# Sheet1.net
KiCad netlist of a schematic drawn in Altium Designer
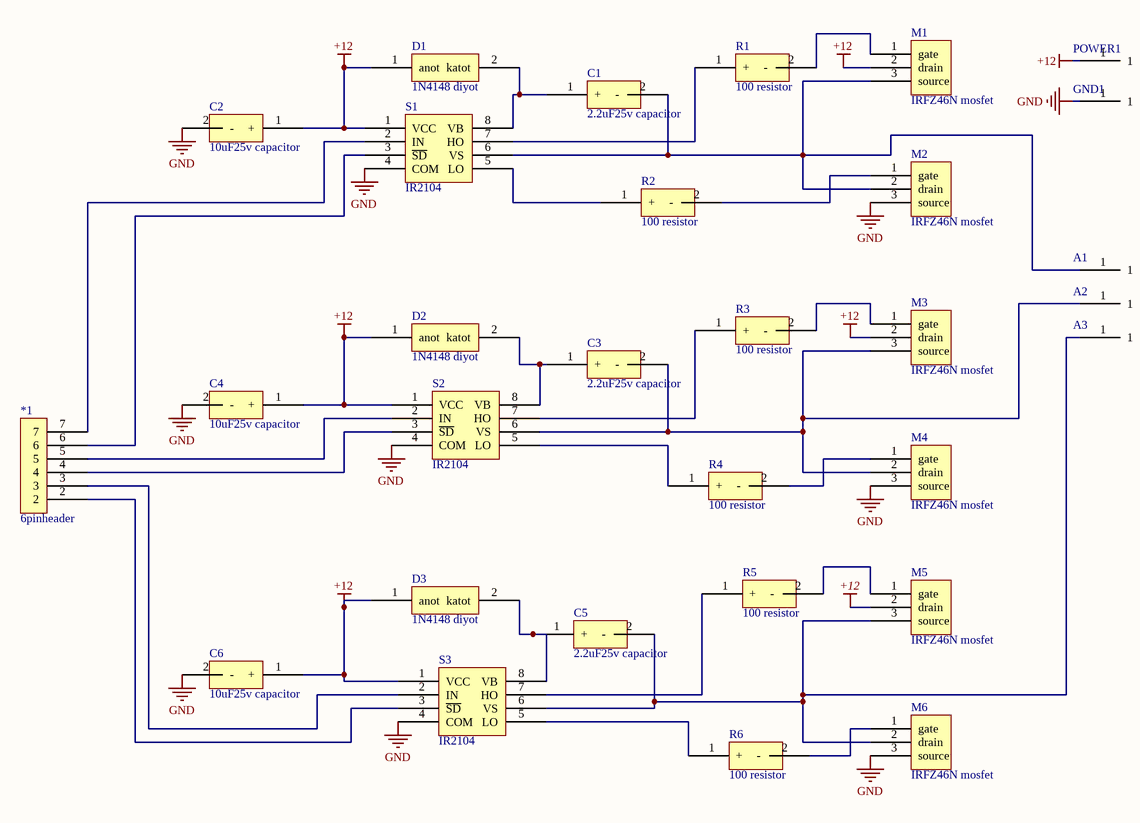
[diagram p0: Sheet1.SchDoc]

(export (version "E")
  (design (tool "Eeschema 10.0.6"))
  (components
    (comp (ref "*1")
      (value "6pinheader")
      (footprint "6pinheader")
      (libsource (lib "Schlib1") (part "6pinheader"))
    )
    (comp (ref "A1") (value "~") (footprint "1pinheader") (libsource (lib "Schlib1") (part "1 pin header")))
    (comp (ref "A2") (value "~") (footprint "1pinheader") (libsource (lib "Schlib1") (part "1 pin header")))
    (comp (ref "A3") (value "~") (footprint "1pinheader") (libsource (lib "Schlib1") (part "1 pin header")))
    (comp (ref "C1")
      (value "2.2uF25v capacitor")
      (footprint "2.2uf25v capacitor")
      (libsource (lib "Schlib1") (part "2.2uF25v capacitor"))
    )
    (comp (ref "C2")
      (value "10uF25v capacitor")
      (footprint "10uf25V capacitor")
      (libsource (lib "Schlib1") (part "10uF25v capacitor"))
    )
    (comp (ref "C3")
      (value "2.2uF25v capacitor")
      (footprint "2.2uf25v capacitor")
      (libsource (lib "Schlib1") (part "2.2uF25v capacitor"))
    )
    (comp (ref "C4")
      (value "10uF25v capacitor")
      (footprint "10uf25V capacitor")
      (libsource (lib "Schlib1") (part "10uF25v capacitor"))
    )
    (comp (ref "C5")
      (value "2.2uF25v capacitor")
      (footprint "2.2uf25v capacitor")
      (libsource (lib "Schlib1") (part "2.2uF25v capacitor"))
    )
    (comp (ref "C6")
      (value "10uF25v capacitor")
      (footprint "10uf25V capacitor")
      (libsource (lib "Schlib1") (part "10uF25v capacitor"))
    )
    (comp (ref "D1")
      (value "1N4148 diyot")
      (footprint "1N4148 diyot")
      (libsource (lib "Schlib1") (part "1N4148 diyot"))
    )
    (comp (ref "D2")
      (value "1N4148 diyot")
      (footprint "1N4148 diyot")
      (libsource (lib "Schlib1") (part "1N4148 diyot"))
    )
    (comp (ref "D3")
      (value "1N4148 diyot")
      (footprint "1N4148 diyot")
      (libsource (lib "Schlib1") (part "1N4148 diyot"))
    )
    (comp (ref "GND1") (value "~") (footprint "1pinheader") (libsource (lib "Schlib1") (part "1 pin header")))
    (comp (ref "M1")
      (value "IRFZ46N mosfet")
      (footprint "IRFZ46N mosfet")
      (libsource (lib "Schlib1") (part "IRFZ46N mosfet"))
    )
    (comp (ref "M2")
      (value "IRFZ46N mosfet")
      (footprint "IRFZ46N mosfet")
      (libsource (lib "Schlib1") (part "IRFZ46N mosfet"))
    )
    (comp (ref "M3")
      (value "IRFZ46N mosfet")
      (footprint "IRFZ46N mosfet")
      (libsource (lib "Schlib1") (part "IRFZ46N mosfet"))
    )
    (comp (ref "M4")
      (value "IRFZ46N mosfet")
      (footprint "IRFZ46N mosfet")
      (libsource (lib "Schlib1") (part "IRFZ46N mosfet"))
    )
    (comp (ref "M5")
      (value "IRFZ46N mosfet")
      (footprint "IRFZ46N mosfet")
      (libsource (lib "Schlib1") (part "IRFZ46N mosfet"))
    )
    (comp (ref "M6")
      (value "IRFZ46N mosfet")
      (footprint "IRFZ46N mosfet")
      (libsource (lib "Schlib1") (part "IRFZ46N mosfet"))
    )
    (comp (ref "POWER1")
      (value "~")
      (footprint "1pinheader")
      (libsource (lib "Schlib1") (part "1 pin header"))
    )
    (comp (ref "R1")
      (value "100 resistor")
      (footprint "100 resistor")
      (libsource (lib "Schlib1") (part "100 resistor"))
    )
    (comp (ref "R2")
      (value "100 resistor")
      (footprint "100 resistor")
      (libsource (lib "Schlib1") (part "100 resistor"))
    )
    (comp (ref "R3")
      (value "100 resistor")
      (footprint "100 resistor")
      (libsource (lib "Schlib1") (part "100 resistor"))
    )
    (comp (ref "R4")
      (value "100 resistor")
      (footprint "100 resistor")
      (libsource (lib "Schlib1") (part "100 resistor"))
    )
    (comp (ref "R5")
      (value "100 resistor")
      (footprint "100 resistor")
      (libsource (lib "Schlib1") (part "100 resistor"))
    )
    (comp (ref "R6")
      (value "100 resistor")
      (footprint "100 resistor")
      (libsource (lib "Schlib1") (part "100 resistor"))
    )
    (comp (ref "S1")
      (value "IR2104")
      (footprint "IR2104 mos sürücü")
      (libsource (lib "Schlib1") (part "IR2104"))
    )
    (comp (ref "S2")
      (value "IR2104")
      (footprint "IR2104 mos sürücü")
      (libsource (lib "Schlib1") (part "IR2104"))
    )
    (comp (ref "S3")
      (value "IR2104")
      (footprint "IR2104 mos sürücü")
      (libsource (lib "Schlib1") (part "IR2104"))
    )
  )
  (nets
    (net (code "1") (name "+12") (class "Default")
      (node (ref "C2") (pin "1") (pinfunction "+_1") (pintype "passive"))
      (node (ref "C4") (pin "1") (pinfunction "+_1") (pintype "passive"))
      (node (ref "C6") (pin "1") (pinfunction "+_1") (pintype "passive"))
      (node (ref "D1") (pin "1") (pinfunction "anot_1") (pintype "passive"))
      (node (ref "D2") (pin "1") (pinfunction "anot_1") (pintype "passive"))
      (node (ref "D3") (pin "1") (pinfunction "anot_1") (pintype "passive"))
      (node (ref "M1") (pin "2") (pinfunction "drain_2") (pintype "passive"))
      (node (ref "M3") (pin "2") (pinfunction "drain_2") (pintype "passive"))
      (node (ref "M5") (pin "2") (pinfunction "drain_2") (pintype "passive"))
      (node (ref "POWER1") (pin "1") (pinfunction "1_1") (pintype "passive"))
      (node (ref "S1") (pin "1") (pinfunction "VCC_1") (pintype "passive"))
      (node (ref "S2") (pin "1") (pinfunction "VCC_1") (pintype "passive"))
      (node (ref "S3") (pin "1") (pinfunction "VCC_1") (pintype "passive"))
    )
    (net (code "2") (name "GND") (class "Default")
      (node (ref "C2") (pin "2") (pinfunction "-_2") (pintype "passive"))
      (node (ref "C4") (pin "2") (pinfunction "-_2") (pintype "passive"))
      (node (ref "C6") (pin "2") (pinfunction "-_2") (pintype "passive"))
      (node (ref "GND1") (pin "1") (pinfunction "1_1") (pintype "passive"))
      (node (ref "M2") (pin "3") (pinfunction "source_3") (pintype "passive"))
      (node (ref "M4") (pin "3") (pinfunction "source_3") (pintype "passive"))
      (node (ref "M6") (pin "3") (pinfunction "source_3") (pintype "passive"))
      (node (ref "S1") (pin "4") (pinfunction "COM_4") (pintype "passive"))
      (node (ref "S2") (pin "4") (pinfunction "COM_4") (pintype "passive"))
      (node (ref "S3") (pin "4") (pinfunction "COM_4") (pintype "passive"))
    )
    (net (code "3") (name "Net-(C1-+)") (class "Default")
      (node (ref "C1") (pin "1") (pinfunction "+_1") (pintype "passive"))
      (node (ref "D1") (pin "2") (pinfunction "katot_2") (pintype "passive"))
      (node (ref "S1") (pin "8") (pinfunction "VB_8") (pintype "passive"))
    )
    (net (code "4") (name "Net-(C1--)") (class "Default")
      (node (ref "A1") (pin "1") (pinfunction "1_1") (pintype "passive"))
      (node (ref "C1") (pin "2") (pinfunction "-_2") (pintype "passive"))
      (node (ref "M1") (pin "3") (pinfunction "source_3") (pintype "passive"))
      (node (ref "M2") (pin "2") (pinfunction "drain_2") (pintype "passive"))
      (node (ref "S1") (pin "6") (pinfunction "VS_6") (pintype "passive"))
    )
    (net (code "5") (name "Net-(C3-+)") (class "Default")
      (node (ref "C3") (pin "1") (pinfunction "+_1") (pintype "passive"))
      (node (ref "D2") (pin "2") (pinfunction "katot_2") (pintype "passive"))
      (node (ref "S2") (pin "8") (pinfunction "VB_8") (pintype "passive"))
    )
    (net (code "6") (name "Net-(C3--)") (class "Default")
      (node (ref "A2") (pin "1") (pinfunction "1_1") (pintype "passive"))
      (node (ref "C3") (pin "2") (pinfunction "-_2") (pintype "passive"))
      (node (ref "M3") (pin "3") (pinfunction "source_3") (pintype "passive"))
      (node (ref "M4") (pin "2") (pinfunction "drain_2") (pintype "passive"))
      (node (ref "S2") (pin "6") (pinfunction "VS_6") (pintype "passive"))
    )
    (net (code "7") (name "Net-(C5-+)") (class "Default")
      (node (ref "C5") (pin "1") (pinfunction "+_1") (pintype "passive"))
      (node (ref "D3") (pin "2") (pinfunction "katot_2") (pintype "passive"))
      (node (ref "S3") (pin "8") (pinfunction "VB_8") (pintype "passive"))
    )
    (net (code "8") (name "Net-(C5--)") (class "Default")
      (node (ref "A3") (pin "1") (pinfunction "1_1") (pintype "passive"))
      (node (ref "C5") (pin "2") (pinfunction "-_2") (pintype "passive"))
      (node (ref "M5") (pin "3") (pinfunction "source_3") (pintype "passive"))
      (node (ref "M6") (pin "2") (pinfunction "drain_2") (pintype "passive"))
      (node (ref "S3") (pin "6") (pinfunction "VS_6") (pintype "passive"))
    )
    (net (code "9") (name "Net-(M1-gate)") (class "Default")
      (node (ref "M1") (pin "1") (pinfunction "gate_1") (pintype "passive"))
      (node (ref "R1") (pin "2") (pinfunction "-_2") (pintype "passive"))
    )
    (net (code "10") (name "Net-(M2-gate)") (class "Default")
      (node (ref "M2") (pin "1") (pinfunction "gate_1") (pintype "passive"))
      (node (ref "R2") (pin "2") (pinfunction "-_2") (pintype "passive"))
    )
    (net (code "11") (name "Net-(M3-gate)") (class "Default")
      (node (ref "M3") (pin "1") (pinfunction "gate_1") (pintype "passive"))
      (node (ref "R3") (pin "2") (pinfunction "-_2") (pintype "passive"))
    )
    (net (code "12") (name "Net-(M4-gate)") (class "Default")
      (node (ref "M4") (pin "1") (pinfunction "gate_1") (pintype "passive"))
      (node (ref "R4") (pin "2") (pinfunction "-_2") (pintype "passive"))
    )
    (net (code "13") (name "Net-(M5-gate)") (class "Default")
      (node (ref "M5") (pin "1") (pinfunction "gate_1") (pintype "passive"))
      (node (ref "R5") (pin "2") (pinfunction "-_2") (pintype "passive"))
    )
    (net (code "14") (name "Net-(M6-gate)") (class "Default")
      (node (ref "M6") (pin "1") (pinfunction "gate_1") (pintype "passive"))
      (node (ref "R6") (pin "2") (pinfunction "-_2") (pintype "passive"))
    )
    (net (code "15") (name "Net-(R1-+)") (class "Default")
      (node (ref "R1") (pin "1") (pinfunction "+_1") (pintype "passive"))
      (node (ref "S1") (pin "7") (pinfunction "HO_7") (pintype "passive"))
    )
    (net (code "16") (name "Net-(R2-+)") (class "Default")
      (node (ref "R2") (pin "1") (pinfunction "+_1") (pintype "passive"))
      (node (ref "S1") (pin "5") (pinfunction "LO_5") (pintype "passive"))
    )
    (net (code "17") (name "Net-(R3-+)") (class "Default")
      (node (ref "R3") (pin "1") (pinfunction "+_1") (pintype "passive"))
      (node (ref "S2") (pin "7") (pinfunction "HO_7") (pintype "passive"))
    )
    (net (code "18") (name "Net-(R4-+)") (class "Default")
      (node (ref "R4") (pin "1") (pinfunction "+_1") (pintype "passive"))
      (node (ref "S2") (pin "5") (pinfunction "LO_5") (pintype "passive"))
    )
    (net (code "19") (name "Net-(R5-+)") (class "Default")
      (node (ref "R5") (pin "1") (pinfunction "+_1") (pintype "passive"))
      (node (ref "S3") (pin "7") (pinfunction "HO_7") (pintype "passive"))
    )
    (net (code "20") (name "Net-(R6-+)") (class "Default")
      (node (ref "R6") (pin "1") (pinfunction "+_1") (pintype "passive"))
      (node (ref "S3") (pin "5") (pinfunction "LO_5") (pintype "passive"))
    )
    (net (code "21") (name "Net-(S1-IN)") (class "Default")
      (node (ref "*1") (pin "7") (pinfunction "7_7") (pintype "passive"))
      (node (ref "S1") (pin "2") (pinfunction "IN_2") (pintype "passive"))
    )
    (net (code "22") (name "Net-(S1-~{SD})") (class "Default")
      (node (ref "*1") (pin "6") (pinfunction "6_6") (pintype "passive"))
      (node (ref "S1") (pin "3") (pinfunction "~{SD}_3") (pintype "passive"))
    )
    (net (code "23") (name "Net-(S2-IN)") (class "Default")
      (node (ref "*1") (pin "5") (pinfunction "5_5") (pintype "passive"))
      (node (ref "S2") (pin "2") (pinfunction "IN_2") (pintype "passive"))
    )
    (net (code "24") (name "Net-(S2-~{SD})") (class "Default")
      (node (ref "*1") (pin "4") (pinfunction "4_4") (pintype "passive"))
      (node (ref "S2") (pin "3") (pinfunction "~{SD}_3") (pintype "passive"))
    )
    (net (code "25") (name "Net-(S3-IN)") (class "Default")
      (node (ref "*1") (pin "3") (pinfunction "3_3") (pintype "passive"))
      (node (ref "S3") (pin "2") (pinfunction "IN_2") (pintype "passive"))
    )
    (net (code "26") (name "Net-(S3-~{SD})") (class "Default")
      (node (ref "*1") (pin "2") (pinfunction "2_2") (pintype "passive"))
      (node (ref "S3") (pin "3") (pinfunction "~{SD}_3") (pintype "passive"))
    )
  )
)
